# Qwiic_Button.net
KiCad netlist of a schematic drawn in EAGLE
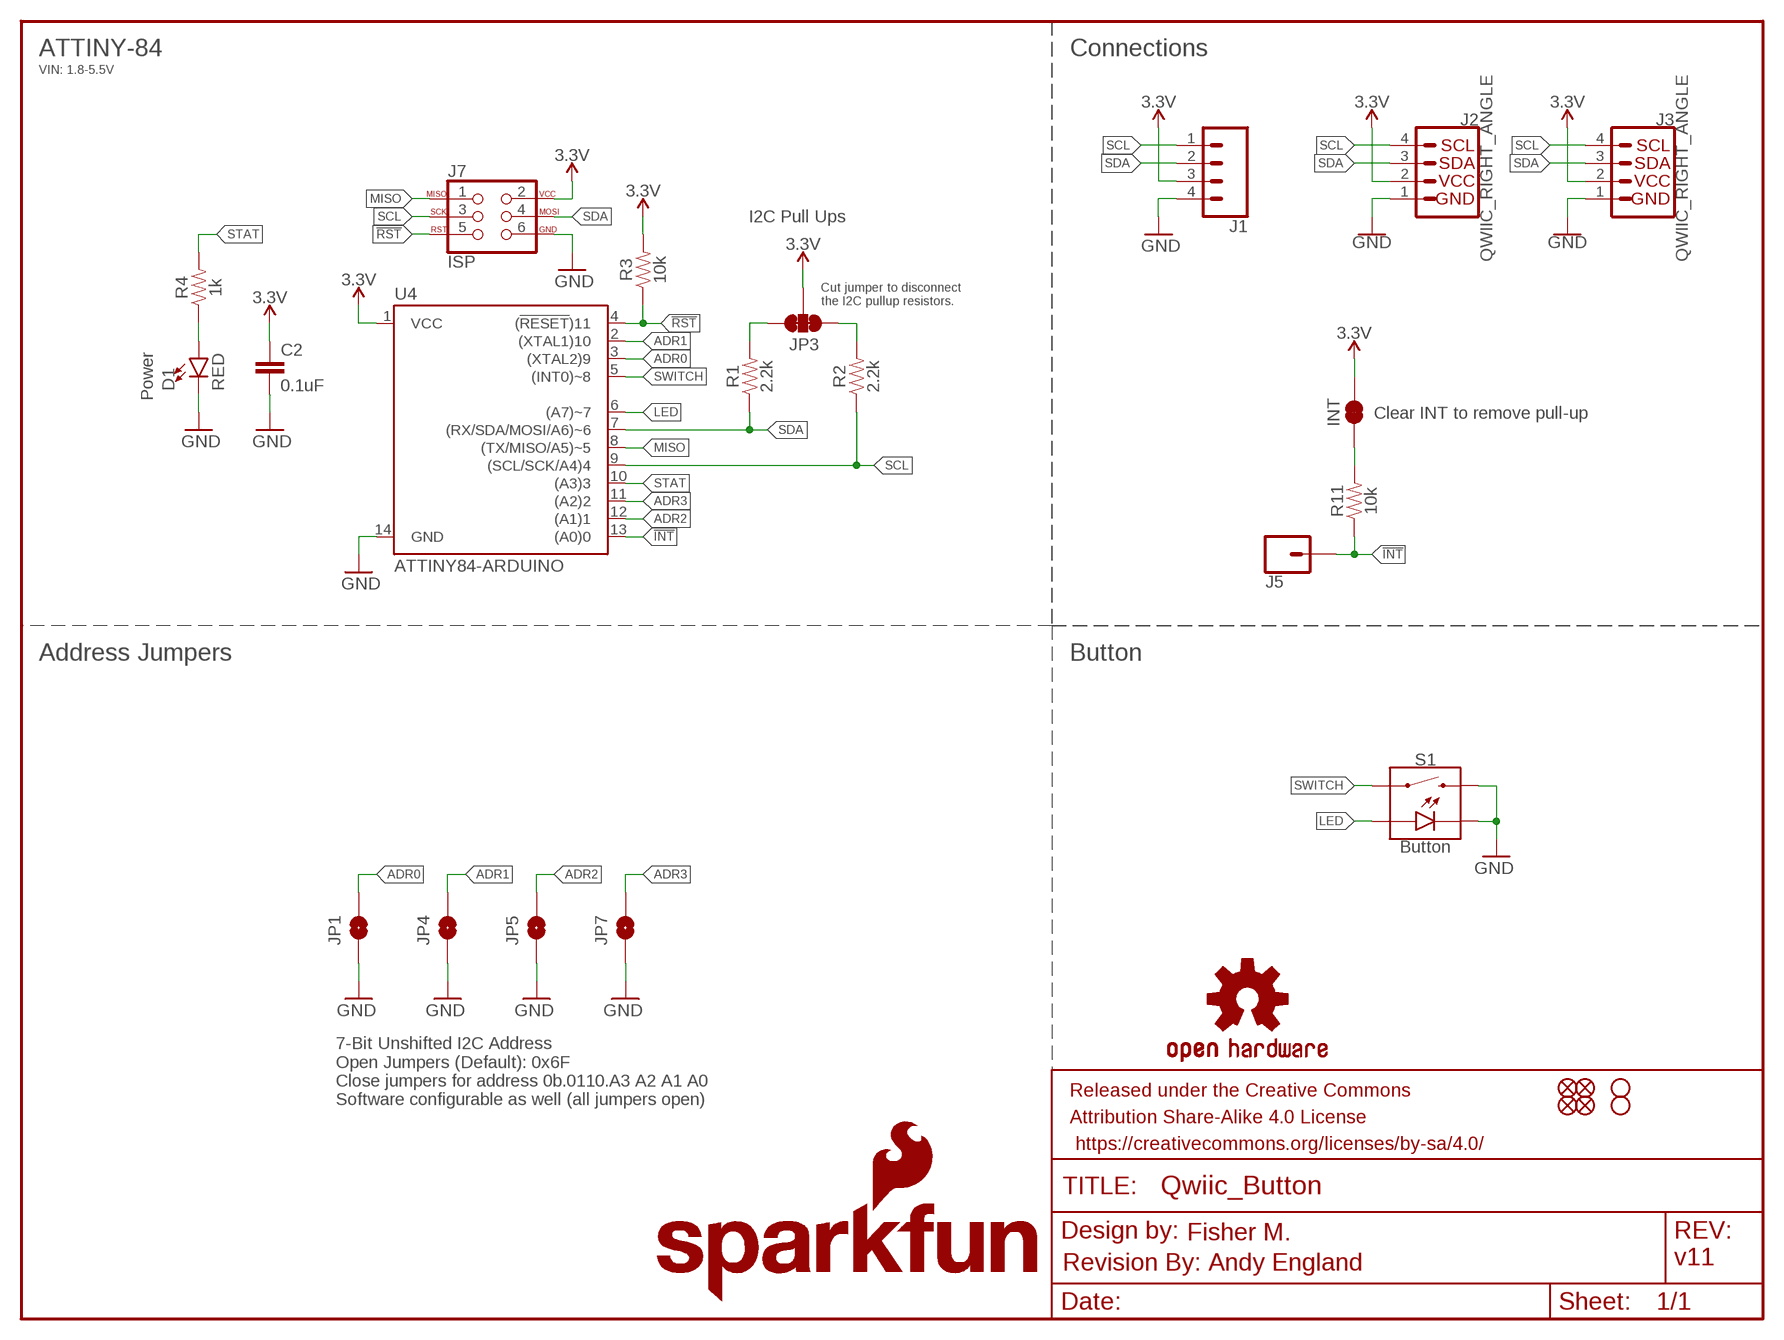
[diagram p0: schematic, sheet 1]

(export (version "E")
  (design (tool "Eeschema 10.0.6"))
  (components
    (comp (ref "C2")
      (value "0.1uF")
      (footprint "eagle-import:0603")
      (libsource (lib "eagle-import") (part "0.1UF-0603-25V-(+80/-20%)"))
    )
    (comp (ref "D1")
      (value "RED")
      (footprint "eagle-import:LED-0603")
      (libsource (lib "eagle-import") (part "LED-RED0603"))
    )
    (comp (ref "FRAME1")
      (value "FRAME-LETTER")
      (footprint "eagle-import:CREATIVE_COMMONS")
      (libsource (lib "eagle-import") (part "FRAME-LETTER"))
    )
    (comp (ref "H1")
      (value "STAND-OFF")
      (footprint "eagle-import:STAND-OFF")
      (libsource (lib "eagle-import") (part "STAND-OFF"))
    )
    (comp (ref "H2")
      (value "STAND-OFF")
      (footprint "eagle-import:STAND-OFF")
      (libsource (lib "eagle-import") (part "STAND-OFF"))
    )
    (comp (ref "INT")
      (value "JUMPER-SMT_2_NC_TRACE_SILK")
      (footprint "eagle-import:SMT-JUMPER_2_NC_TRACE_SILK")
      (libsource (lib "eagle-import") (part "JUMPER-SMT_2_NC_TRACE_SILK"))
    )
    (comp (ref "J1")
      (value "CONN_041X04_NO_SILK")
      (footprint "eagle-import:1X04_NO_SILK")
      (libsource (lib "eagle-import") (part "CONN_041X04_NO_SILK"))
    )
    (comp (ref "J2")
      (value "QWIIC_RIGHT_ANGLE")
      (footprint "eagle-import:JST04_1MM_RA")
      (libsource (lib "eagle-import") (part "QWIIC_CONNECTORJS-1MM"))
    )
    (comp (ref "J3")
      (value "QWIIC_RIGHT_ANGLE")
      (footprint "eagle-import:JST04_1MM_RA")
      (libsource (lib "eagle-import") (part "QWIIC_CONNECTORJS-1MM"))
    )
    (comp (ref "J5")
      (value "CONN_01PTH_NO_SILK_YES_STOP")
      (footprint "eagle-import:1X01_NO_SILK")
      (libsource (lib "eagle-import") (part "CONN_01PTH_NO_SILK_YES_STOP"))
    )
    (comp (ref "J7")
      (value "ISP")
      (footprint "eagle-import:2X3_TEST_POINTS")
      (libsource (lib "eagle-import") (part "AVR_SPI_PROG_3X2TESTPOINTS"))
    )
    (comp (ref "JP1")
      (value "JUMPER-SMT_2_NO_NO-SILK")
      (footprint "eagle-import:SMT-JUMPER_2_NO_NO-SILK")
      (libsource (lib "eagle-import") (part "JUMPER-SMT_2_NO_NO-SILK"))
    )
    (comp (ref "JP2")
      (value "FIDUCIALUFIDUCIAL")
      (footprint "eagle-import:MICRO-FIDUCIAL")
      (libsource (lib "eagle-import") (part "FIDUCIALUFIDUCIAL"))
    )
    (comp (ref "JP3")
      (value "JUMPER-SMT_3_2-NC_TRACE_SILK")
      (footprint "eagle-import:SMT-JUMPER_3_2-NC_TRACE_SILK")
      (libsource (lib "eagle-import") (part "JUMPER-SMT_3_2-NC_TRACE_SILK"))
    )
    (comp (ref "JP4")
      (value "JUMPER-SMT_2_NO_NO-SILK")
      (footprint "eagle-import:SMT-JUMPER_2_NO_NO-SILK")
      (libsource (lib "eagle-import") (part "JUMPER-SMT_2_NO_NO-SILK"))
    )
    (comp (ref "JP5")
      (value "JUMPER-SMT_2_NO_NO-SILK")
      (footprint "eagle-import:SMT-JUMPER_2_NO_NO-SILK")
      (libsource (lib "eagle-import") (part "JUMPER-SMT_2_NO_NO-SILK"))
    )
    (comp (ref "JP6")
      (value "FIDUCIALUFIDUCIAL")
      (footprint "eagle-import:MICRO-FIDUCIAL")
      (libsource (lib "eagle-import") (part "FIDUCIALUFIDUCIAL"))
    )
    (comp (ref "JP7")
      (value "JUMPER-SMT_2_NO_NO-SILK")
      (footprint "eagle-import:SMT-JUMPER_2_NO_NO-SILK")
      (libsource (lib "eagle-import") (part "JUMPER-SMT_2_NO_NO-SILK"))
    )
    (comp (ref "JP8")
      (value "FIDUCIALUFIDUCIAL")
      (footprint "eagle-import:MICRO-FIDUCIAL")
      (libsource (lib "eagle-import") (part "FIDUCIALUFIDUCIAL"))
    )
    (comp (ref "JP9")
      (value "FIDUCIALUFIDUCIAL")
      (footprint "eagle-import:MICRO-FIDUCIAL")
      (libsource (lib "eagle-import") (part "FIDUCIALUFIDUCIAL"))
    )
    (comp (ref "LOGO1")
      (value "OSHW-LOGOMINI")
      (footprint "eagle-import:OSHW-LOGO-MINI")
      (libsource (lib "eagle-import") (part "OSHW-LOGOMINI"))
    )
    (comp (ref "LOGO2")
      (value "REVISION")
      (footprint "eagle-import:REVISION")
      (libsource (lib "eagle-import") (part "REVISION"))
    )
    (comp (ref "LOGO3")
      (value "SFE_LOGO_NAME.1_INCH")
      (footprint "eagle-import:SFE_LOGO_NAME_.1")
      (libsource (lib "eagle-import") (part "SFE_LOGO_NAME.1_INCH"))
    )
    (comp (ref "LOGO4")
      (value "SFE_LOGO_FLAME.1_INCH")
      (footprint "eagle-import:SFE_LOGO_FLAME_.1")
      (libsource (lib "eagle-import") (part "SFE_LOGO_FLAME.1_INCH"))
    )
    (comp (ref "R1")
      (value "2.2k")
      (footprint "eagle-import:0603")
      (libsource (lib "eagle-import") (part "2.2KOHM-0603-1/10W-1%"))
    )
    (comp (ref "R2")
      (value "2.2k")
      (footprint "eagle-import:0603")
      (libsource (lib "eagle-import") (part "2.2KOHM-0603-1/10W-1%"))
    )
    (comp (ref "R3")
      (value "10k")
      (footprint "eagle-import:0603")
      (libsource (lib "eagle-import") (part "10KOHM-0603-1/10W-1%"))
    )
    (comp (ref "R4")
      (value "1k")
      (footprint "eagle-import:0603")
      (libsource (lib "eagle-import") (part "1KOHM-0603-1/10W-1%"))
    )
    (comp (ref "R11")
      (value "10k")
      (footprint "eagle-import:0603")
      (libsource (lib "eagle-import") (part "10KOHM-0603-1/10W-1%"))
    )
    (comp (ref "S1")
      (value "Button")
      (footprint "eagle-import:TACTILE_SWITCH_LED_PTH_12MM")
      (libsource (lib "eagle-import") (part "MOMENTARY-SWITCH-SPST-LED-PTH-12MM"))
    )
    (comp (ref "U4")
      (value "ATTINY84-ARDUINO")
      (footprint "eagle-import:SO14")
      (libsource (lib "eagle-import") (part "ATTINY84-ARDUINO"))
    )
  )
  (nets
    (net (code "1") (name "/~{INT}") (class "Default")
      (node (ref "J5") (pin "1") (pinfunction "1_1") (pintype "passive"))
      (node (ref "R11") (pin "1") (pinfunction "1_1") (pintype "passive"))
      (node (ref "U4") (pin "13") (pinfunction "(A0)0_13") (pintype "bidirectional"))
    )
    (net (code "2") (name "/~{RST}") (class "Default")
      (node (ref "J7") (pin "5") (pinfunction "5_5") (pintype "passive"))
      (node (ref "R3") (pin "1") (pinfunction "1_1") (pintype "passive"))
      (node (ref "U4") (pin "4") (pinfunction "(~{RESET})11_4") (pintype "bidirectional"))
    )
    (net (code "3") (name "3.3V") (class "Default")
      (node (ref "C2") (pin "1") (pinfunction "1_1") (pintype "passive"))
      (node (ref "INT") (pin "2") (pinfunction "2_2") (pintype "passive"))
      (node (ref "J1") (pin "3") (pinfunction "3_3") (pintype "passive"))
      (node (ref "J2") (pin "2") (pinfunction "2_2") (pintype "power_in"))
      (node (ref "J3") (pin "2") (pinfunction "2_2") (pintype "power_in"))
      (node (ref "J7") (pin "2") (pinfunction "2_2") (pintype "passive"))
      (node (ref "JP3") (pin "2") (pinfunction "2_2") (pintype "passive"))
      (node (ref "R3") (pin "2") (pinfunction "2_2") (pintype "passive"))
      (node (ref "U4") (pin "1") (pinfunction "VCC_1") (pintype "bidirectional"))
    )
    (net (code "4") (name "ADR0") (class "Default")
      (node (ref "JP1") (pin "2") (pinfunction "2_2") (pintype "passive"))
      (node (ref "U4") (pin "3") (pinfunction "(XTAL2)9_3") (pintype "bidirectional"))
    )
    (net (code "5") (name "ADR1") (class "Default")
      (node (ref "JP4") (pin "2") (pinfunction "2_2") (pintype "passive"))
      (node (ref "U4") (pin "2") (pinfunction "(XTAL1)10_2") (pintype "bidirectional"))
    )
    (net (code "6") (name "ADR2") (class "Default")
      (node (ref "JP5") (pin "2") (pinfunction "2_2") (pintype "passive"))
      (node (ref "U4") (pin "12") (pinfunction "(A1)1_12") (pintype "bidirectional"))
    )
    (net (code "7") (name "ADR3") (class "Default")
      (node (ref "JP7") (pin "2") (pinfunction "2_2") (pintype "passive"))
      (node (ref "U4") (pin "11") (pinfunction "(A2)2_11") (pintype "bidirectional"))
    )
    (net (code "8") (name "GND") (class "Default")
      (node (ref "C2") (pin "2") (pinfunction "2_2") (pintype "passive"))
      (node (ref "D1") (pin "C") (pinfunction "C_C") (pintype "passive"))
      (node (ref "J1") (pin "4") (pinfunction "4_4") (pintype "passive"))
      (node (ref "J2") (pin "1") (pinfunction "1_1") (pintype "power_in"))
      (node (ref "J3") (pin "1") (pinfunction "1_1") (pintype "power_in"))
      (node (ref "J7") (pin "6") (pinfunction "6_6") (pintype "passive"))
      (node (ref "JP1") (pin "1") (pinfunction "1_1") (pintype "passive"))
      (node (ref "JP4") (pin "1") (pinfunction "1_1") (pintype "passive"))
      (node (ref "JP5") (pin "1") (pinfunction "1_1") (pintype "passive"))
      (node (ref "JP7") (pin "1") (pinfunction "1_1") (pintype "passive"))
      (node (ref "S1") (pin "2") (pinfunction "2_2") (pintype "passive"))
      (node (ref "S1") (pin "C") (pinfunction "C_C") (pintype "passive"))
      (node (ref "U4") (pin "14") (pinfunction "GND_14") (pintype "bidirectional"))
    )
    (net (code "9") (name "LED") (class "Default")
      (node (ref "S1") (pin "A") (pinfunction "A_A") (pintype "passive"))
      (node (ref "U4") (pin "6") (pinfunction "(A7)~{7}_6") (pintype "bidirectional"))
    )
    (net (code "10") (name "MISO") (class "Default")
      (node (ref "J7") (pin "1") (pinfunction "1_1") (pintype "passive"))
      (node (ref "U4") (pin "8") (pinfunction "(TX/MISO/A5)~{5}_8") (pintype "bidirectional"))
    )
    (net (code "11") (name "Net-(D1-PadA)") (class "Default")
      (node (ref "D1") (pin "A") (pinfunction "A_A") (pintype "passive"))
      (node (ref "R4") (pin "1") (pinfunction "1_1") (pintype "passive"))
    )
    (net (code "12") (name "Net-(INT-Pad1)") (class "Default")
      (node (ref "INT") (pin "1") (pinfunction "1_1") (pintype "passive"))
      (node (ref "R11") (pin "2") (pinfunction "2_2") (pintype "passive"))
    )
    (net (code "13") (name "Net-(JP3-Pad1)") (class "Default")
      (node (ref "JP3") (pin "1") (pinfunction "1_1") (pintype "passive"))
      (node (ref "R2") (pin "2") (pinfunction "2_2") (pintype "passive"))
    )
    (net (code "14") (name "Net-(JP3-Pad3)") (class "Default")
      (node (ref "JP3") (pin "3") (pinfunction "3_3") (pintype "passive"))
      (node (ref "R1") (pin "2") (pinfunction "2_2") (pintype "passive"))
    )
    (net (code "15") (name "SCL") (class "Default")
      (node (ref "J1") (pin "1") (pinfunction "1_1") (pintype "passive"))
      (node (ref "J2") (pin "4") (pinfunction "4_4") (pintype "passive"))
      (node (ref "J3") (pin "4") (pinfunction "4_4") (pintype "passive"))
      (node (ref "J7") (pin "3") (pinfunction "3_3") (pintype "passive"))
      (node (ref "R2") (pin "1") (pinfunction "1_1") (pintype "passive"))
      (node (ref "U4") (pin "9") (pinfunction "(SCL/SCK/A4)4_9") (pintype "bidirectional"))
    )
    (net (code "16") (name "SDA") (class "Default")
      (node (ref "J1") (pin "2") (pinfunction "2_2") (pintype "passive"))
      (node (ref "J2") (pin "3") (pinfunction "3_3") (pintype "passive"))
      (node (ref "J3") (pin "3") (pinfunction "3_3") (pintype "passive"))
      (node (ref "J7") (pin "4") (pinfunction "4_4") (pintype "passive"))
      (node (ref "R1") (pin "1") (pinfunction "1_1") (pintype "passive"))
      (node (ref "U4") (pin "7") (pinfunction "(RX/SDA/MOSI/A6)~{6}_7") (pintype "bidirectional"))
    )
    (net (code "17") (name "STAT") (class "Default")
      (node (ref "R4") (pin "2") (pinfunction "2_2") (pintype "passive"))
      (node (ref "U4") (pin "10") (pinfunction "(A3)3_10") (pintype "bidirectional"))
    )
    (net (code "18") (name "SWITCH") (class "Default")
      (node (ref "S1") (pin "4") (pinfunction "1_4") (pintype "passive"))
      (node (ref "U4") (pin "5") (pinfunction "(INT0)~{8}_5") (pintype "bidirectional"))
    )
  )
)
